# SCH_RAILWAY_TRACK_CRACK_DETECTION_SYSTEM.net
KiCad netlist of a schematic drawn in EasyEDA
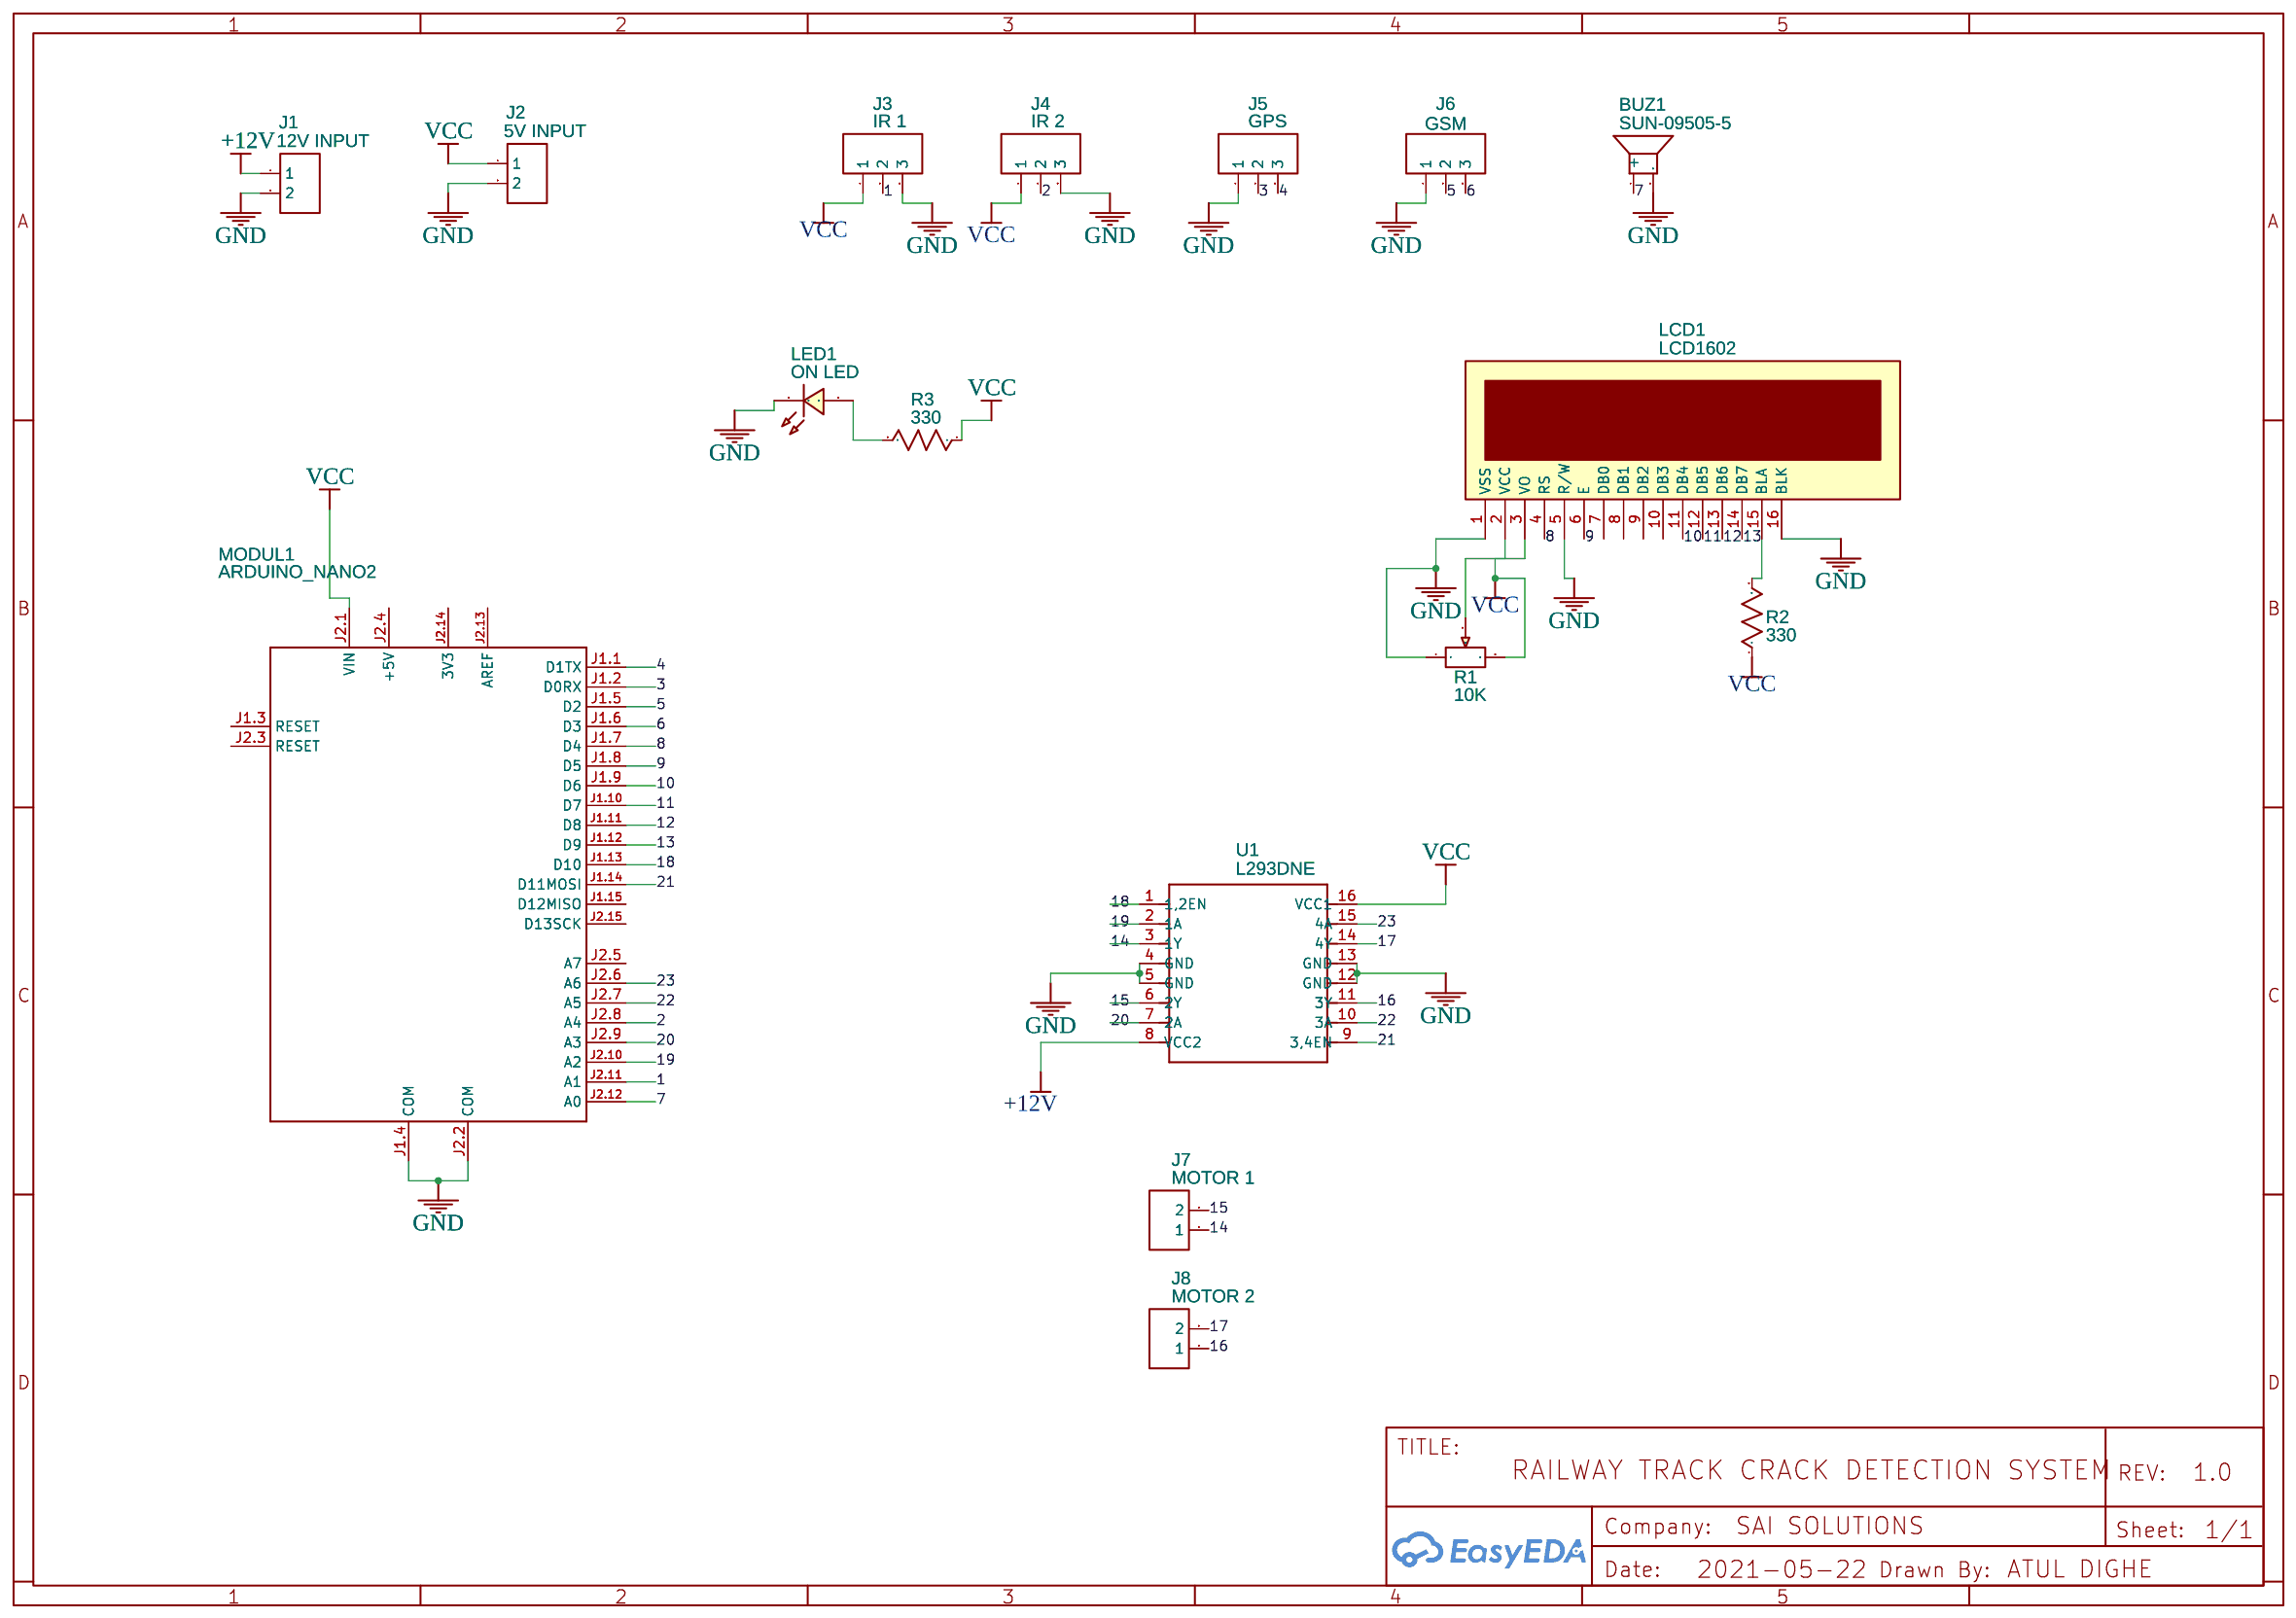
[diagram p0: schematic sheet]

(export (version "E")
  (design (tool "Eeschema 10.0.6"))
  (components
    (comp (ref "BUZ1")
      (value "SUN-09505-5")
      (fields (field (name "BOM_Supplier Part") "C2862"))
      (libsource (lib "") (part "SUN-09505-5"))
    )
    (comp (ref "J1")
      (value "12V INPUT")
      (fields (field (name "BOM_Supplier Part") "C124375"))
      (libsource (lib "") (part "HDR-M-2.54_1x2"))
    )
    (comp (ref "J2")
      (value "5V INPUT")
      (fields (field (name "BOM_Supplier Part") "C124375"))
      (libsource (lib "") (part "HDR-M-2.54_1x2"))
    )
    (comp (ref "J3")
      (value "IR 1")
      (fields (field (name "BOM_Supplier Part") "C180248"))
      (libsource (lib "") (part "HDR-M-2.54_1x3"))
    )
    (comp (ref "J4")
      (value "IR 2")
      (fields (field (name "BOM_Supplier Part") "C180248"))
      (libsource (lib "") (part "HDR-M-2.54_1x3"))
    )
    (comp (ref "J5")
      (value "GPS")
      (fields (field (name "BOM_Supplier Part") "C180248"))
      (libsource (lib "") (part "HDR-M-2.54_1x3"))
    )
    (comp (ref "J6")
      (value "GSM")
      (fields (field (name "BOM_Supplier Part") "C180248"))
      (libsource (lib "") (part "HDR-M-2.54_1x3"))
    )
    (comp (ref "J7")
      (value "MOTOR 1")
      (fields (field (name "BOM_Supplier Part") "C124375"))
      (libsource (lib "") (part "HDR-M-2.54_1x2_1"))
    )
    (comp (ref "J8")
      (value "MOTOR 2")
      (fields (field (name "BOM_Supplier Part") "C124375"))
      (libsource (lib "") (part "HDR-M-2.54_1x2_1"))
    )
    (comp (ref "LCD1")
      (value "LCD1602")
      (fields
        (field (name "BOM_Manufacturer Part") "LCM1602K-NSW-BBW")
        (field (name "BOM_Supplier Part") "C83275")
      )
      (libsource (lib "") (part "LCD1602"))
    )
    (comp (ref "LED1")
      (value "ON LED")
      (fields
        (field (name "BOM_Manufacturer Part") "333-2SURD/S530-A3")
        (field (name "BOM_Supplier Part") "C87271")
      )
      (libsource (lib "") (part "LED-TH-5mm_R"))
    )
    (comp (ref "MODUL1") (value "ARDUINO_NANO2") (libsource (lib "") (part "ARDUINO_NANO2")))
    (comp (ref "R1")
      (value "10K")
      (fields
        (field (name "BOM_Manufacturer Part") "RM063-103 10K")
        (field (name "BOM_Supplier Part") "C38793")
      )
      (libsource (lib "") (part "RM063-103 10K"))
    )
    (comp (ref "R2") (value "330") (libsource (lib "") (part "R_AXIAL-0.4_US_1")))
    (comp (ref "R3") (value "330") (libsource (lib "") (part "R_AXIAL-0.4_US")))
    (comp (ref "U1") (value "L293DNE") (libsource (lib "") (part "L293DNE")))
  )
  (nets
    (net (code "1") (name "+12V") (class "Default")
      (node (ref "J1") (pin "1") (pinfunction "1_1") (pintype "unspecified"))
      (node (ref "U1") (pin "8") (pinfunction "VCC2_8") (pintype "unspecified"))
    )
    (net (code "2") (name "/1") (class "Default")
      (node (ref "J3") (pin "2") (pinfunction "2_2") (pintype "input"))
      (node (ref "MODUL1") (pin "J2.11") (pinfunction "A1_J2.11") (pintype "unspecified"))
    )
    (net (code "3") (name "/2") (class "Default")
      (node (ref "J4") (pin "2") (pinfunction "2_2") (pintype "input"))
      (node (ref "MODUL1") (pin "J2.8") (pinfunction "A4_J2.8") (pintype "unspecified"))
    )
    (net (code "4") (name "/3") (class "Default")
      (node (ref "J5") (pin "2") (pinfunction "2_2") (pintype "input"))
      (node (ref "MODUL1") (pin "J1.2") (pinfunction "D0RX_J1.2") (pintype "unspecified"))
    )
    (net (code "5") (name "/4") (class "Default")
      (node (ref "J5") (pin "3") (pinfunction "3_3") (pintype "input"))
      (node (ref "MODUL1") (pin "J1.1") (pinfunction "D1TX_J1.1") (pintype "unspecified"))
    )
    (net (code "6") (name "/5") (class "Default")
      (node (ref "J6") (pin "2") (pinfunction "2_2") (pintype "input"))
      (node (ref "MODUL1") (pin "J1.5") (pinfunction "D2_J1.5") (pintype "unspecified"))
    )
    (net (code "7") (name "/6") (class "Default")
      (node (ref "J6") (pin "3") (pinfunction "3_3") (pintype "input"))
      (node (ref "MODUL1") (pin "J1.6") (pinfunction "D3_J1.6") (pintype "unspecified"))
    )
    (net (code "8") (name "/7") (class "Default")
      (node (ref "BUZ1") (pin "1") (pinfunction "+_1") (pintype "unspecified"))
      (node (ref "MODUL1") (pin "J2.12") (pinfunction "A0_J2.12") (pintype "unspecified"))
    )
    (net (code "9") (name "/8") (class "Default")
      (node (ref "LCD1") (pin "4") (pinfunction "RS_4") (pintype "unspecified"))
      (node (ref "MODUL1") (pin "J1.7") (pinfunction "D4_J1.7") (pintype "unspecified"))
    )
    (net (code "10") (name "/9") (class "Default")
      (node (ref "LCD1") (pin "6") (pinfunction "E_6") (pintype "unspecified"))
      (node (ref "MODUL1") (pin "J1.8") (pinfunction "D5_J1.8") (pintype "unspecified"))
    )
    (net (code "11") (name "/10") (class "Default")
      (node (ref "LCD1") (pin "11") (pinfunction "DB4_11") (pintype "unspecified"))
      (node (ref "MODUL1") (pin "J1.9") (pinfunction "D6_J1.9") (pintype "unspecified"))
    )
    (net (code "12") (name "/11") (class "Default")
      (node (ref "LCD1") (pin "12") (pinfunction "DB5_12") (pintype "unspecified"))
      (node (ref "MODUL1") (pin "J1.10") (pinfunction "D7_J1.10") (pintype "unspecified"))
    )
    (net (code "13") (name "/12") (class "Default")
      (node (ref "LCD1") (pin "13") (pinfunction "DB6_13") (pintype "unspecified"))
      (node (ref "MODUL1") (pin "J1.11") (pinfunction "D8_J1.11") (pintype "unspecified"))
    )
    (net (code "14") (name "/13") (class "Default")
      (node (ref "LCD1") (pin "14") (pinfunction "DB7_14") (pintype "unspecified"))
      (node (ref "MODUL1") (pin "J1.12") (pinfunction "D9_J1.12") (pintype "unspecified"))
    )
    (net (code "15") (name "/14") (class "Default")
      (node (ref "J7") (pin "1") (pinfunction "1_1") (pintype "unspecified"))
      (node (ref "U1") (pin "3") (pinfunction "1Y_3") (pintype "unspecified"))
    )
    (net (code "16") (name "/15") (class "Default")
      (node (ref "J7") (pin "2") (pinfunction "2_2") (pintype "unspecified"))
      (node (ref "U1") (pin "6") (pinfunction "2Y_6") (pintype "unspecified"))
    )
    (net (code "17") (name "/16") (class "Default")
      (node (ref "J8") (pin "1") (pinfunction "1_1") (pintype "unspecified"))
      (node (ref "U1") (pin "11") (pinfunction "3Y_11") (pintype "unspecified"))
    )
    (net (code "18") (name "/17") (class "Default")
      (node (ref "J8") (pin "2") (pinfunction "2_2") (pintype "unspecified"))
      (node (ref "U1") (pin "14") (pinfunction "4Y_14") (pintype "unspecified"))
    )
    (net (code "19") (name "/18") (class "Default")
      (node (ref "MODUL1") (pin "J1.13") (pinfunction "D10_J1.13") (pintype "unspecified"))
      (node (ref "U1") (pin "1") (pinfunction "1,2EN_1") (pintype "unspecified"))
    )
    (net (code "20") (name "/19") (class "Default")
      (node (ref "MODUL1") (pin "J2.10") (pinfunction "A2_J2.10") (pintype "unspecified"))
      (node (ref "U1") (pin "2") (pinfunction "1A_2") (pintype "unspecified"))
    )
    (net (code "21") (name "/20") (class "Default")
      (node (ref "MODUL1") (pin "J2.9") (pinfunction "A3_J2.9") (pintype "unspecified"))
      (node (ref "U1") (pin "7") (pinfunction "2A_7") (pintype "unspecified"))
    )
    (net (code "22") (name "/21") (class "Default")
      (node (ref "MODUL1") (pin "J1.14") (pinfunction "D11MOSI_J1.14") (pintype "unspecified"))
      (node (ref "U1") (pin "9") (pinfunction "3,4EN_9") (pintype "unspecified"))
    )
    (net (code "23") (name "/22") (class "Default")
      (node (ref "MODUL1") (pin "J2.7") (pinfunction "A5_J2.7") (pintype "unspecified"))
      (node (ref "U1") (pin "10") (pinfunction "3A_10") (pintype "unspecified"))
    )
    (net (code "24") (name "/23") (class "Default")
      (node (ref "MODUL1") (pin "J2.6") (pinfunction "A6_J2.6") (pintype "unspecified"))
      (node (ref "U1") (pin "15") (pinfunction "4A_15") (pintype "unspecified"))
    )
    (net (code "25") (name "GND") (class "Default")
      (node (ref "BUZ1") (pin "2") (pinfunction "2_2") (pintype "unspecified"))
      (node (ref "J1") (pin "2") (pinfunction "2_2") (pintype "unspecified"))
      (node (ref "J2") (pin "2") (pinfunction "2_2") (pintype "unspecified"))
      (node (ref "J3") (pin "3") (pinfunction "3_3") (pintype "input"))
      (node (ref "J4") (pin "3") (pinfunction "3_3") (pintype "input"))
      (node (ref "J5") (pin "1") (pinfunction "1_1") (pintype "input"))
      (node (ref "J6") (pin "1") (pinfunction "1_1") (pintype "input"))
      (node (ref "LCD1") (pin "1") (pinfunction "VSS_1") (pintype "unspecified"))
      (node (ref "LCD1") (pin "16") (pinfunction "BLK_16") (pintype "unspecified"))
      (node (ref "LCD1") (pin "5") (pinfunction "R/W_5") (pintype "unspecified"))
      (node (ref "LED1") (pin "2") (pinfunction "2_2") (pintype "unspecified"))
      (node (ref "MODUL1") (pin "J1.4") (pinfunction "COM_J1.4") (pintype "passive"))
      (node (ref "MODUL1") (pin "J2.2") (pinfunction "COM_J2.2") (pintype "passive"))
      (node (ref "R1") (pin "1") (pinfunction "1_1") (pintype "input"))
      (node (ref "U1") (pin "12") (pinfunction "GND_12") (pintype "unspecified"))
      (node (ref "U1") (pin "13") (pinfunction "GND_13") (pintype "unspecified"))
      (node (ref "U1") (pin "4") (pinfunction "GND_4") (pintype "unspecified"))
      (node (ref "U1") (pin "5") (pinfunction "GND_5") (pintype "unspecified"))
    )
    (net (code "26") (name "Net-(LCD1-BLA)") (class "Default")
      (node (ref "LCD1") (pin "15") (pinfunction "BLA_15") (pintype "unspecified"))
      (node (ref "R2") (pin "2") (pinfunction "2_2") (pintype "unspecified"))
    )
    (net (code "27") (name "Net-(LCD1-VO)") (class "Default")
      (node (ref "LCD1") (pin "3") (pinfunction "VO_3") (pintype "unspecified"))
      (node (ref "R1") (pin "2") (pinfunction "2_2") (pintype "input"))
    )
    (net (code "28") (name "Net-(LED1-Pad1)") (class "Default")
      (node (ref "LED1") (pin "1") (pinfunction "1_1") (pintype "unspecified"))
      (node (ref "R3") (pin "2") (pinfunction "2_2") (pintype "unspecified"))
    )
    (net (code "29") (name "VCC") (class "Default")
      (node (ref "J2") (pin "1") (pinfunction "1_1") (pintype "unspecified"))
      (node (ref "J3") (pin "1") (pinfunction "1_1") (pintype "input"))
      (node (ref "J4") (pin "1") (pinfunction "1_1") (pintype "input"))
      (node (ref "LCD1") (pin "2") (pinfunction "VCC_2") (pintype "unspecified"))
      (node (ref "MODUL1") (pin "J2.1") (pinfunction "VIN_J2.1") (pintype "passive"))
      (node (ref "R1") (pin "3") (pinfunction "3_3") (pintype "input"))
      (node (ref "R2") (pin "1") (pinfunction "1_1") (pintype "unspecified"))
      (node (ref "R3") (pin "1") (pinfunction "1_1") (pintype "unspecified"))
      (node (ref "U1") (pin "16") (pinfunction "VCC1_16") (pintype "unspecified"))
    )
    (net (code "30") (name "unconnected-(LCD1-DB0-Pad7)") (class "Default")
      (node (ref "LCD1") (pin "7") (pinfunction "DB0_7") (pintype "unspecified"))
    )
    (net (code "31") (name "unconnected-(LCD1-DB1-Pad8)") (class "Default")
      (node (ref "LCD1") (pin "8") (pinfunction "DB1_8") (pintype "unspecified"))
    )
    (net (code "32") (name "unconnected-(LCD1-DB2-Pad9)") (class "Default")
      (node (ref "LCD1") (pin "9") (pinfunction "DB2_9") (pintype "unspecified"))
    )
    (net (code "33") (name "unconnected-(LCD1-DB3-Pad10)") (class "Default")
      (node (ref "LCD1") (pin "10") (pinfunction "DB3_10") (pintype "unspecified"))
    )
    (net (code "34") (name "unconnected-(MODUL1-+5V-PadJ2.4)") (class "Default")
      (node (ref "MODUL1") (pin "J2.4") (pinfunction "+5V_J2.4") (pintype "passive"))
    )
    (net (code "35") (name "unconnected-(MODUL1-3V3-PadJ2.14)") (class "Default")
      (node (ref "MODUL1") (pin "J2.14") (pinfunction "3V3_J2.14") (pintype "passive"))
    )
    (net (code "36") (name "unconnected-(MODUL1-A7-PadJ2.5)") (class "Default")
      (node (ref "MODUL1") (pin "J2.5") (pinfunction "A7_J2.5") (pintype "unspecified"))
    )
    (net (code "37") (name "unconnected-(MODUL1-AREF-PadJ2.13)") (class "Default")
      (node (ref "MODUL1") (pin "J2.13") (pinfunction "AREF_J2.13") (pintype "passive"))
    )
    (net (code "38") (name "unconnected-(MODUL1-D12MISO-PadJ1.15)") (class "Default")
      (node (ref "MODUL1") (pin "J1.15") (pinfunction "D12MISO_J1.15") (pintype "unspecified"))
    )
    (net (code "39") (name "unconnected-(MODUL1-D13SCK-PadJ2.15)") (class "Default")
      (node (ref "MODUL1") (pin "J2.15") (pinfunction "D13SCK_J2.15") (pintype "unspecified"))
    )
    (net (code "40") (name "unconnected-(MODUL1-RESET-PadJ1.3)") (class "Default")
      (node (ref "MODUL1") (pin "J1.3") (pinfunction "RESET_J1.3") (pintype "unspecified"))
    )
    (net (code "41") (name "unconnected-(MODUL1-RESET-PadJ2.3)") (class "Default")
      (node (ref "MODUL1") (pin "J2.3") (pinfunction "RESET_J2.3") (pintype "unspecified"))
    )
  )
)
